# bt-snes-aa-ncp1402-attiny25-isp.net
KiCad netlist of a schematic drawn in EAGLE
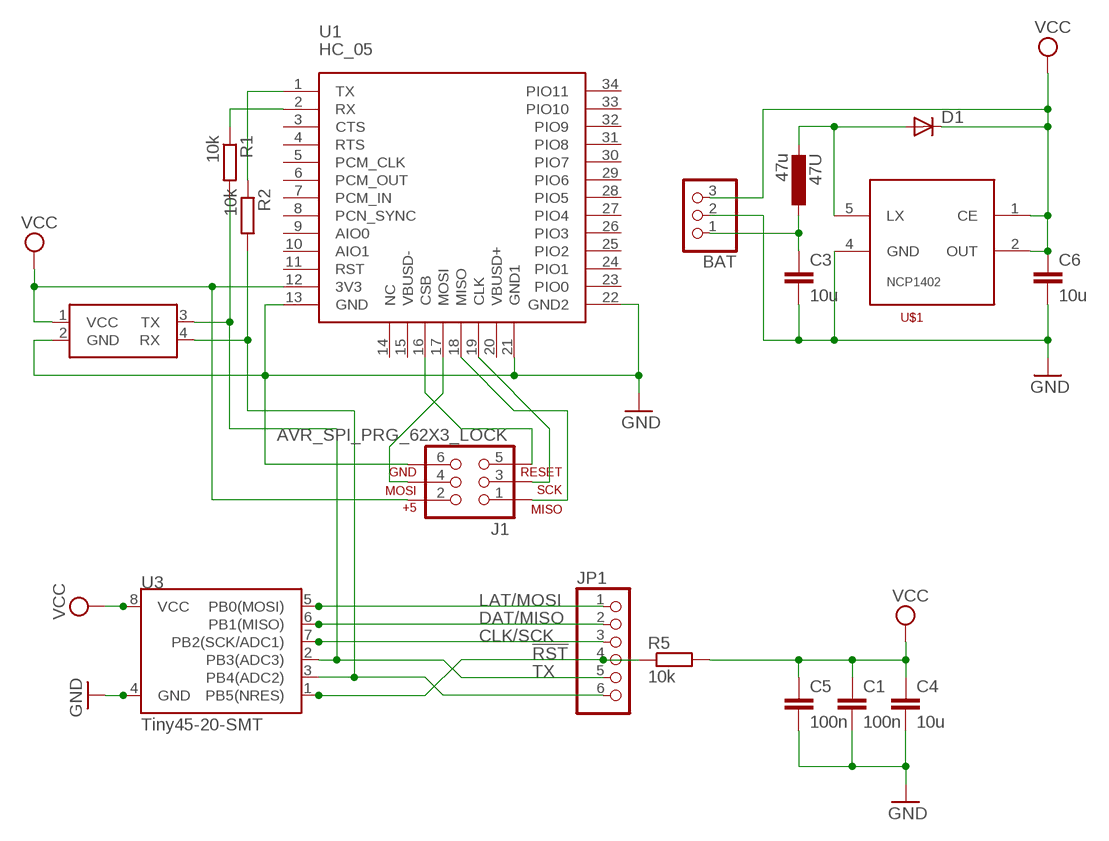
[diagram p0: schematic, sheet 1]

(export (version "E")
  (design (tool "Eeschema 10.0.6"))
  (components
    (comp (ref "47U")
      (value "47u")
      (footprint "eagle-import:C1210")
      (libsource (lib "eagle-import") (part "L-EUL1210"))
    )
    (comp (ref "BAT")
      (value "PINHD-1X3")
      (footprint "eagle-import:1X03")
      (libsource (lib "eagle-import") (part "PINHD-1X3"))
    )
    (comp (ref "C1")
      (value "100n")
      (footprint "eagle-import:C0805K")
      (libsource (lib "eagle-import") (part "C-EUC0805K"))
    )
    (comp (ref "C3")
      (value "10u")
      (footprint "eagle-import:C0805K")
      (libsource (lib "eagle-import") (part "C-EUC0805K"))
    )
    (comp (ref "C4")
      (value "10u")
      (footprint "eagle-import:C0805K")
      (libsource (lib "eagle-import") (part "C-EUC0805K"))
    )
    (comp (ref "C5")
      (value "100n")
      (footprint "eagle-import:C0805K")
      (libsource (lib "eagle-import") (part "C-EUC0805K"))
    )
    (comp (ref "C6")
      (value "10u")
      (footprint "eagle-import:C0805K")
      (libsource (lib "eagle-import") (part "C-EUC0805K"))
    )
    (comp (ref "D1")
      (value "DIODE-SOD80C")
      (footprint "eagle-import:SOD80C")
      (libsource (lib "eagle-import") (part "DIODE-SOD80C"))
    )
    (comp (ref "J1")
      (value "AVR_SPI_PRG_62X3_LOCK")
      (footprint "eagle-import:2X3_LOCK")
      (libsource (lib "eagle-import") (part "AVR_SPI_PRG_62X3_LOCK"))
    )
    (comp (ref "JP1")
      (value "PINHD-1X6")
      (footprint "eagle-import:1X06")
      (libsource (lib "eagle-import") (part "PINHD-1X6"))
    )
    (comp (ref "R1")
      (value "10k")
      (footprint "eagle-import:M0805")
      (libsource (lib "eagle-import") (part "R-EU_M0805"))
    )
    (comp (ref "R2")
      (value "10k")
      (footprint "eagle-import:M0805")
      (libsource (lib "eagle-import") (part "R-EU_M0805"))
    )
    (comp (ref "R5")
      (value "10k")
      (footprint "eagle-import:M0805")
      (libsource (lib "eagle-import") (part "R-EU_M0805"))
    )
    (comp (ref "U$1")
      (value "NCP1402-SOT23-5")
      (footprint "eagle-import:SOT23-5")
      (libsource (lib "eagle-import") (part "NCP1402-SOT23-5"))
    )
    (comp (ref "U$2")
      (value "UART_CONN")
      (footprint "eagle-import:UART_CONN_LOCK")
      (libsource (lib "eagle-import") (part "UART_CONN"))
    )
    (comp (ref "U1")
      (value "HC_05")
      (footprint "eagle-import:BLUETOOTH_SMD")
      (libsource (lib "eagle-import") (part "HC_05"))
    )
    (comp (ref "U3")
      (value "Tiny45-20-SMT")
      (footprint "eagle-import:SO08-EIAJ")
      (libsource (lib "eagle-import") (part "ATTINY45TINY45-20-SMT"))
    )
  )
  (nets
    (net (code "1") (name "/CLK{slash}SCK") (class "Default")
      (node (ref "JP1") (pin "3") (pinfunction "3_3") (pintype "passive"))
      (node (ref "U3") (pin "7") (pinfunction "PB2(SCK/ADC1)_7") (pintype "bidirectional"))
    )
    (net (code "2") (name "/DAT{slash}MISO") (class "Default")
      (node (ref "JP1") (pin "2") (pinfunction "2_2") (pintype "passive"))
      (node (ref "U3") (pin "6") (pinfunction "PB1(MISO)_6") (pintype "bidirectional"))
    )
    (net (code "3") (name "/LAT{slash}MOSI") (class "Default")
      (node (ref "JP1") (pin "1") (pinfunction "1_1") (pintype "passive"))
      (node (ref "U3") (pin "5") (pinfunction "PB0(MOSI)_5") (pintype "bidirectional"))
    )
    (net (code "4") (name "/TX") (class "Default")
      (node (ref "JP1") (pin "5") (pinfunction "5_5") (pintype "passive"))
      (node (ref "R1") (pin "2") (pinfunction "2_2") (pintype "passive"))
      (node (ref "U$2") (pin "3") (pinfunction "TX_3") (pintype "bidirectional"))
      (node (ref "U3") (pin "2") (pinfunction "PB3(ADC3)_2") (pintype "bidirectional"))
    )
    (net (code "5") (name "/~{RST}") (class "Default")
      (node (ref "JP1") (pin "4") (pinfunction "4_4") (pintype "passive"))
      (node (ref "R5") (pin "1") (pinfunction "1_1") (pintype "passive"))
      (node (ref "U3") (pin "1") (pinfunction "PB5(NRES)_1") (pintype "bidirectional"))
    )
    (net (code "6") (name "GND") (class "Default")
      (node (ref "BAT") (pin "2") (pinfunction "2_2") (pintype "passive"))
      (node (ref "C1") (pin "2") (pinfunction "2_2") (pintype "passive"))
      (node (ref "C3") (pin "2") (pinfunction "2_2") (pintype "passive"))
      (node (ref "C4") (pin "2") (pinfunction "2_2") (pintype "passive"))
      (node (ref "C5") (pin "2") (pinfunction "2_2") (pintype "passive"))
      (node (ref "C6") (pin "2") (pinfunction "2_2") (pintype "passive"))
      (node (ref "J1") (pin "6") (pinfunction "6_6") (pintype "passive"))
      (node (ref "U$1") (pin "4") (pinfunction "GND_4") (pintype "bidirectional"))
      (node (ref "U$2") (pin "2") (pinfunction "GND_2") (pintype "bidirectional"))
      (node (ref "U1") (pin "13") (pinfunction "GND_13") (pintype "bidirectional"))
      (node (ref "U1") (pin "21") (pinfunction "GND1_21") (pintype "bidirectional"))
      (node (ref "U1") (pin "22") (pinfunction "GND2_22") (pintype "bidirectional"))
      (node (ref "U3") (pin "4") (pinfunction "GND_4") (pintype "bidirectional"))
    )
    (net (code "7") (name "Net-(47U-Pad1)") (class "Default")
      (node (ref "47U") (pin "1") (pinfunction "1_1") (pintype "passive"))
      (node (ref "BAT") (pin "1") (pinfunction "1_1") (pintype "passive"))
      (node (ref "C3") (pin "1") (pinfunction "1_1") (pintype "passive"))
    )
    (net (code "8") (name "Net-(U$1-LX)") (class "Default")
      (node (ref "47U") (pin "2") (pinfunction "2_2") (pintype "passive"))
      (node (ref "D1") (pin "A") (pinfunction "A_A") (pintype "passive"))
      (node (ref "U$1") (pin "5") (pinfunction "LX_5") (pintype "bidirectional"))
    )
    (net (code "9") (name "Net-(U$2-RX)") (class "Default")
      (node (ref "JP1") (pin "6") (pinfunction "6_6") (pintype "passive"))
      (node (ref "R2") (pin "2") (pinfunction "2_2") (pintype "passive"))
      (node (ref "U$2") (pin "4") (pinfunction "RX_4") (pintype "bidirectional"))
      (node (ref "U3") (pin "3") (pinfunction "PB4(ADC2)_3") (pintype "bidirectional"))
    )
    (net (code "10") (name "Net-(U1-CLK)") (class "Default")
      (node (ref "J1") (pin "3") (pinfunction "3_3") (pintype "passive"))
      (node (ref "U1") (pin "19") (pinfunction "CLK_19") (pintype "bidirectional"))
    )
    (net (code "11") (name "Net-(U1-CSB)") (class "Default")
      (node (ref "J1") (pin "5") (pinfunction "5_5") (pintype "passive"))
      (node (ref "U1") (pin "16") (pinfunction "CSB_16") (pintype "bidirectional"))
    )
    (net (code "12") (name "Net-(U1-MISO)") (class "Default")
      (node (ref "J1") (pin "1") (pinfunction "1_1") (pintype "passive"))
      (node (ref "U1") (pin "18") (pinfunction "MISO_18") (pintype "bidirectional"))
    )
    (net (code "13") (name "Net-(U1-MOSI)") (class "Default")
      (node (ref "J1") (pin "4") (pinfunction "4_4") (pintype "passive"))
      (node (ref "U1") (pin "17") (pinfunction "MOSI_17") (pintype "bidirectional"))
    )
    (net (code "14") (name "Net-(U1-RX)") (class "Default")
      (node (ref "R1") (pin "1") (pinfunction "1_1") (pintype "passive"))
      (node (ref "U1") (pin "2") (pinfunction "RX_2") (pintype "bidirectional"))
    )
    (net (code "15") (name "Net-(U1-TX)") (class "Default")
      (node (ref "R2") (pin "1") (pinfunction "1_1") (pintype "passive"))
      (node (ref "U1") (pin "1") (pinfunction "TX_1") (pintype "bidirectional"))
    )
    (net (code "16") (name "VCC") (class "Default")
      (node (ref "BAT") (pin "3") (pinfunction "3_3") (pintype "passive"))
      (node (ref "C1") (pin "1") (pinfunction "1_1") (pintype "passive"))
      (node (ref "C4") (pin "1") (pinfunction "1_1") (pintype "passive"))
      (node (ref "C5") (pin "1") (pinfunction "1_1") (pintype "passive"))
      (node (ref "C6") (pin "1") (pinfunction "1_1") (pintype "passive"))
      (node (ref "D1") (pin "C") (pinfunction "C_C") (pintype "passive"))
      (node (ref "J1") (pin "2") (pinfunction "2_2") (pintype "passive"))
      (node (ref "R5") (pin "2") (pinfunction "2_2") (pintype "passive"))
      (node (ref "U$1") (pin "1") (pinfunction "CE_1") (pintype "bidirectional"))
      (node (ref "U$1") (pin "2") (pinfunction "OUT_2") (pintype "bidirectional"))
      (node (ref "U$2") (pin "1") (pinfunction "VCC_1") (pintype "bidirectional"))
      (node (ref "U1") (pin "12") (pinfunction "3V3_12") (pintype "bidirectional"))
      (node (ref "U3") (pin "8") (pinfunction "VCC_8") (pintype "bidirectional"))
    )
    (net (code "17") (name "unconnected-(U1-AIO0-Pad9)") (class "Default")
      (node (ref "U1") (pin "9") (pinfunction "AIO0_9") (pintype "bidirectional"))
    )
    (net (code "18") (name "unconnected-(U1-AIO1-Pad10)") (class "Default")
      (node (ref "U1") (pin "10") (pinfunction "AIO1_10") (pintype "bidirectional"))
    )
    (net (code "19") (name "unconnected-(U1-CTS-Pad3)") (class "Default")
      (node (ref "U1") (pin "3") (pinfunction "CTS_3") (pintype "bidirectional"))
    )
    (net (code "20") (name "unconnected-(U1-NC-Pad14)") (class "Default")
      (node (ref "U1") (pin "14") (pinfunction "NC_14") (pintype "bidirectional"))
    )
    (net (code "21") (name "unconnected-(U1-PCM_CLK-Pad5)") (class "Default")
      (node (ref "U1") (pin "5") (pinfunction "PCM_CLK_5") (pintype "bidirectional"))
    )
    (net (code "22") (name "unconnected-(U1-PCM_IN-Pad7)") (class "Default")
      (node (ref "U1") (pin "7") (pinfunction "PCM_IN_7") (pintype "bidirectional"))
    )
    (net (code "23") (name "unconnected-(U1-PCM_OUT-Pad6)") (class "Default")
      (node (ref "U1") (pin "6") (pinfunction "PCM_OUT_6") (pintype "bidirectional"))
    )
    (net (code "24") (name "unconnected-(U1-PCN_SYNC-Pad8)") (class "Default")
      (node (ref "U1") (pin "8") (pinfunction "PCN_SYNC_8") (pintype "bidirectional"))
    )
    (net (code "25") (name "unconnected-(U1-PIO0-Pad23)") (class "Default")
      (node (ref "U1") (pin "23") (pinfunction "PIO0_23") (pintype "bidirectional"))
    )
    (net (code "26") (name "unconnected-(U1-PIO1-Pad24)") (class "Default")
      (node (ref "U1") (pin "24") (pinfunction "PIO1_24") (pintype "bidirectional"))
    )
    (net (code "27") (name "unconnected-(U1-PIO2-Pad25)") (class "Default")
      (node (ref "U1") (pin "25") (pinfunction "PIO2_25") (pintype "bidirectional"))
    )
    (net (code "28") (name "unconnected-(U1-PIO3-Pad26)") (class "Default")
      (node (ref "U1") (pin "26") (pinfunction "PIO3_26") (pintype "bidirectional"))
    )
    (net (code "29") (name "unconnected-(U1-PIO4-Pad27)") (class "Default")
      (node (ref "U1") (pin "27") (pinfunction "PIO4_27") (pintype "bidirectional"))
    )
    (net (code "30") (name "unconnected-(U1-PIO5-Pad28)") (class "Default")
      (node (ref "U1") (pin "28") (pinfunction "PIO5_28") (pintype "bidirectional"))
    )
    (net (code "31") (name "unconnected-(U1-PIO6-Pad29)") (class "Default")
      (node (ref "U1") (pin "29") (pinfunction "PIO6_29") (pintype "bidirectional"))
    )
    (net (code "32") (name "unconnected-(U1-PIO7-Pad30)") (class "Default")
      (node (ref "U1") (pin "30") (pinfunction "PIO7_30") (pintype "bidirectional"))
    )
    (net (code "33") (name "unconnected-(U1-PIO8-Pad31)") (class "Default")
      (node (ref "U1") (pin "31") (pinfunction "PIO8_31") (pintype "bidirectional"))
    )
    (net (code "34") (name "unconnected-(U1-PIO9-Pad32)") (class "Default")
      (node (ref "U1") (pin "32") (pinfunction "PIO9_32") (pintype "bidirectional"))
    )
    (net (code "35") (name "unconnected-(U1-PIO10-Pad33)") (class "Default")
      (node (ref "U1") (pin "33") (pinfunction "PIO10_33") (pintype "bidirectional"))
    )
    (net (code "36") (name "unconnected-(U1-PIO11-Pad34)") (class "Default")
      (node (ref "U1") (pin "34") (pinfunction "PIO11_34") (pintype "bidirectional"))
    )
    (net (code "37") (name "unconnected-(U1-RST-Pad11)") (class "Default")
      (node (ref "U1") (pin "11") (pinfunction "RST_11") (pintype "bidirectional"))
    )
    (net (code "38") (name "unconnected-(U1-RTS-Pad4)") (class "Default")
      (node (ref "U1") (pin "4") (pinfunction "RTS_4") (pintype "bidirectional"))
    )
    (net (code "39") (name "unconnected-(U1-VBUSD+-Pad20)") (class "Default")
      (node (ref "U1") (pin "20") (pinfunction "VBUSD+_20") (pintype "bidirectional"))
    )
    (net (code "40") (name "unconnected-(U1-VBUSD--Pad15)") (class "Default")
      (node (ref "U1") (pin "15") (pinfunction "VBUSD-_15") (pintype "bidirectional"))
    )
  )
)
